# Doorbell.net
KiCad netlist of a schematic drawn in EAGLE
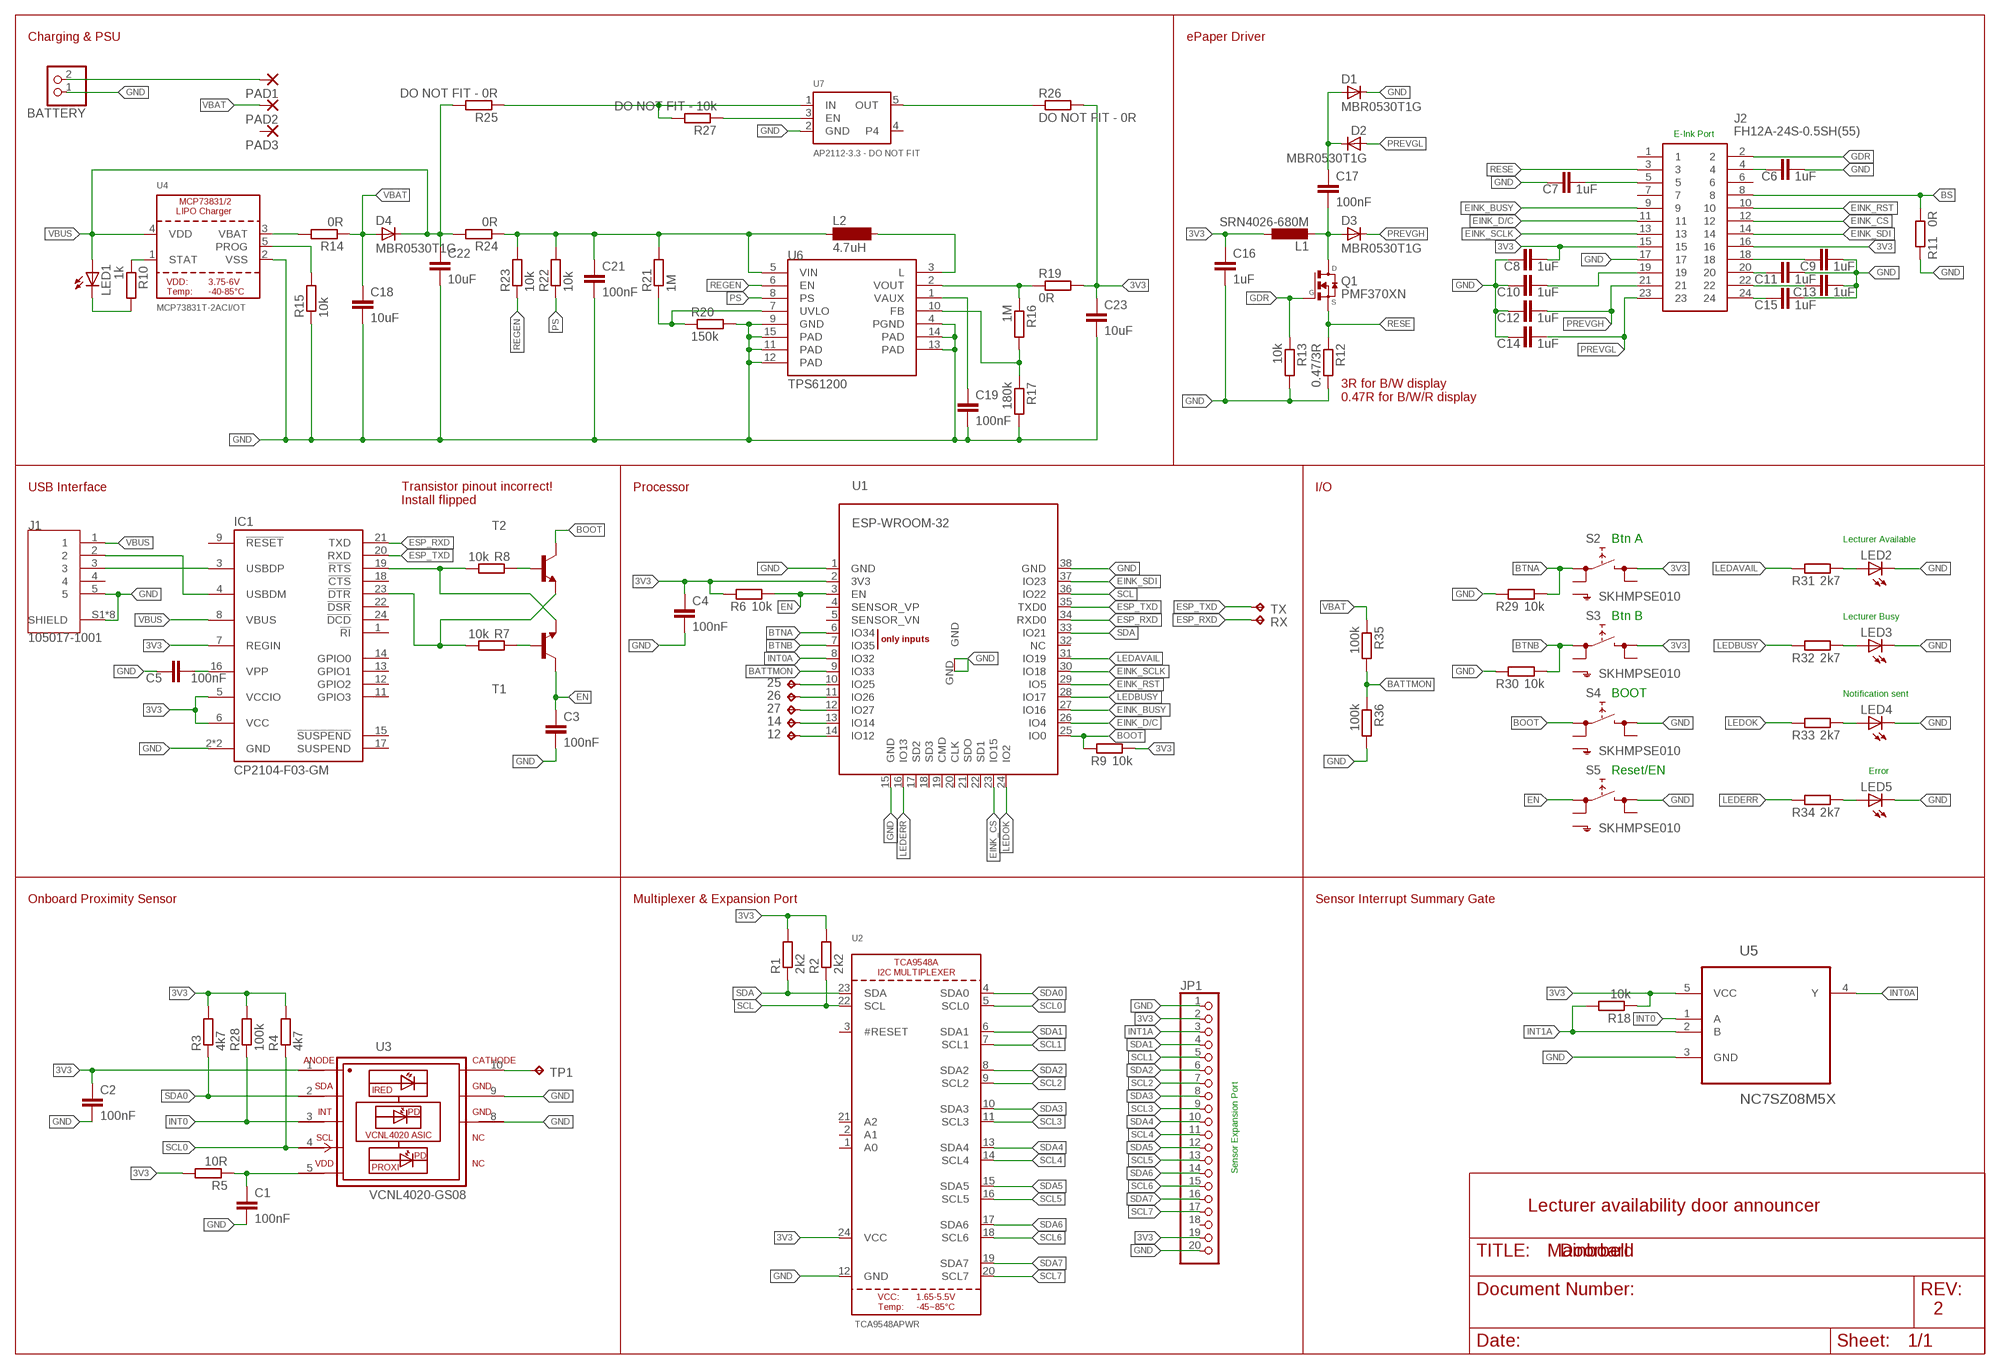
[diagram p0: schematic, sheet 1]

(export (version "E")
  (design (tool "Eeschema 10.0.6"))
  (components
    (comp (ref "12")
      (value "TPB1,27")
      (footprint "eagle-import:B1,27")
      (libsource (lib "eagle-import") (part "TPB1,27"))
    )
    (comp (ref "14")
      (value "TPB1,27")
      (footprint "eagle-import:B1,27")
      (libsource (lib "eagle-import") (part "TPB1,27"))
    )
    (comp (ref "25")
      (value "TPB1,27")
      (footprint "eagle-import:B1,27")
      (libsource (lib "eagle-import") (part "TPB1,27"))
    )
    (comp (ref "26")
      (value "TPB1,27")
      (footprint "eagle-import:B1,27")
      (libsource (lib "eagle-import") (part "TPB1,27"))
    )
    (comp (ref "27")
      (value "TPB1,27")
      (footprint "eagle-import:B1,27")
      (libsource (lib "eagle-import") (part "TPB1,27"))
    )
    (comp (ref "BATTERY")
      (value "PINHD-1X2/90")
      (footprint "eagle-import:1X02_90")
      (libsource (lib "eagle-import") (part "PINHD-1X2/90"))
    )
    (comp (ref "C1")
      (value "100nF")
      (footprint "eagle-import:C0603")
      (libsource (lib "eagle-import") (part "C-EUC0603"))
    )
    (comp (ref "C2")
      (value "100nF")
      (footprint "eagle-import:C0603")
      (libsource (lib "eagle-import") (part "C-EUC0603"))
    )
    (comp (ref "C3")
      (value "100nF")
      (footprint "eagle-import:C0603")
      (libsource (lib "eagle-import") (part "C-EUC0603"))
    )
    (comp (ref "C4")
      (value "100nF")
      (footprint "eagle-import:C0603")
      (libsource (lib "eagle-import") (part "C-EUC0603"))
    )
    (comp (ref "C5")
      (value "100nF")
      (footprint "eagle-import:C0603")
      (libsource (lib "eagle-import") (part "C-EUC0603"))
    )
    (comp (ref "C6")
      (value "1uF")
      (footprint "eagle-import:C0603")
      (libsource (lib "eagle-import") (part "C-EUC0603"))
    )
    (comp (ref "C7")
      (value "1uF")
      (footprint "eagle-import:C0603")
      (libsource (lib "eagle-import") (part "C-EUC0603"))
    )
    (comp (ref "C8")
      (value "1uF")
      (footprint "eagle-import:C0603")
      (libsource (lib "eagle-import") (part "C-EUC0603"))
    )
    (comp (ref "C9")
      (value "1uF")
      (footprint "eagle-import:C0603")
      (libsource (lib "eagle-import") (part "C-EUC0603"))
    )
    (comp (ref "C10")
      (value "1uF")
      (footprint "eagle-import:C0603")
      (libsource (lib "eagle-import") (part "C-EUC0603"))
    )
    (comp (ref "C11")
      (value "1uF")
      (footprint "eagle-import:C0603")
      (libsource (lib "eagle-import") (part "C-EUC0603"))
    )
    (comp (ref "C12")
      (value "1uF")
      (footprint "eagle-import:C0603")
      (libsource (lib "eagle-import") (part "C-EUC0603"))
    )
    (comp (ref "C13")
      (value "1uF")
      (footprint "eagle-import:C0603")
      (libsource (lib "eagle-import") (part "C-EUC0603"))
    )
    (comp (ref "C14")
      (value "1uF")
      (footprint "eagle-import:C0603")
      (libsource (lib "eagle-import") (part "C-EUC0603"))
    )
    (comp (ref "C15")
      (value "1uF")
      (footprint "eagle-import:C0603")
      (libsource (lib "eagle-import") (part "C-EUC0603"))
    )
    (comp (ref "C16")
      (value "1uF")
      (footprint "eagle-import:C0603")
      (libsource (lib "eagle-import") (part "C-EUC0603"))
    )
    (comp (ref "C17")
      (value "100nF")
      (footprint "eagle-import:C0603")
      (libsource (lib "eagle-import") (part "C-EUC0603"))
    )
    (comp (ref "C18")
      (value "10uF")
      (footprint "eagle-import:C1206")
      (libsource (lib "eagle-import") (part "C-EUC1206"))
    )
    (comp (ref "C19")
      (value "100nF")
      (footprint "eagle-import:C0603")
      (libsource (lib "eagle-import") (part "C-EUC0603"))
    )
    (comp (ref "C21")
      (value "100nF")
      (footprint "eagle-import:C0603")
      (libsource (lib "eagle-import") (part "C-EUC0603"))
    )
    (comp (ref "C22")
      (value "10uF")
      (footprint "eagle-import:C1206")
      (libsource (lib "eagle-import") (part "C-EUC1206"))
    )
    (comp (ref "C23")
      (value "10uF")
      (footprint "eagle-import:C1206")
      (libsource (lib "eagle-import") (part "C-EUC1206"))
    )
    (comp (ref "D1")
      (value "MBR0530T1G")
      (footprint "eagle-import:SOD123")
      (libsource (lib "eagle-import") (part "D-SOD123"))
    )
    (comp (ref "D2")
      (value "MBR0530T1G")
      (footprint "eagle-import:SOD123")
      (libsource (lib "eagle-import") (part "D-SOD123"))
    )
    (comp (ref "D3")
      (value "MBR0530T1G")
      (footprint "eagle-import:SOD123")
      (libsource (lib "eagle-import") (part "D-SOD123"))
    )
    (comp (ref "D4")
      (value "MBR0530T1G")
      (footprint "eagle-import:SOD123")
      (libsource (lib "eagle-import") (part "D-SOD123"))
    )
    (comp (ref "IC1")
      (value "CP2104-F03-GM")
      (footprint "eagle-import:QFN24-PAD")
      (fields (field (name "MF") "Silicon Labs") (field (name "MP") "CP2104"))
      (libsource (lib "eagle-import") (part "CP2104-F03-GM"))
    )
    (comp (ref "J1")
      (value "105017-1001")
      (footprint "eagle-import:MOLEX_105017-1001")
      (fields (field (name "MF") "Molex"))
      (libsource (lib "eagle-import") (part "105017-1001"))
    )
    (comp (ref "J2")
      (value "FH12A-24S-0.5SH(55)")
      (footprint "eagle-import:FH12A-24S-0.5SH")
      (fields (field (name "MOUSER_PART_NUMBER") "798-FH12A-24S0.5SH55"))
      (libsource (lib "eagle-import") (part "FH12A-24S-0.5SH(55)"))
    )
    (comp (ref "JP1")
      (value "PINHD-1X20/90")
      (footprint "eagle-import:1X20_90")
      (libsource (lib "eagle-import") (part "PINHD-1X20/90"))
    )
    (comp (ref "L1")
      (value "SRN4026-680M")
      (footprint "eagle-import:L4532P")
      (libsource (lib "eagle-import") (part "L-EUL4532P"))
    )
    (comp (ref "L2")
      (value "4.7uH")
      (footprint "eagle-import:MS50")
      (libsource (lib "eagle-import") (part "MS50"))
    )
    (comp (ref "LED1")
      (value "LEDSML0603")
      (footprint "eagle-import:SML0603")
      (libsource (lib "eagle-import") (part "LEDSML0603"))
    )
    (comp (ref "LED2")
      (value "LEDSML0603")
      (footprint "eagle-import:SML0603")
      (libsource (lib "eagle-import") (part "LEDSML0603"))
    )
    (comp (ref "LED3")
      (value "LEDSML0603")
      (footprint "eagle-import:SML0603")
      (libsource (lib "eagle-import") (part "LEDSML0603"))
    )
    (comp (ref "LED4")
      (value "LEDSML0603")
      (footprint "eagle-import:SML0603")
      (libsource (lib "eagle-import") (part "LEDSML0603"))
    )
    (comp (ref "LED5")
      (value "LEDSML0603")
      (footprint "eagle-import:SML0603")
      (libsource (lib "eagle-import") (part "LEDSML0603"))
    )
    (comp (ref "PAD1")
      (value "WIREPADSMD1,27-254")
      (footprint "eagle-import:SMD1,27-2,54")
      (libsource (lib "eagle-import") (part "WIREPADSMD1,27-254"))
    )
    (comp (ref "PAD2")
      (value "WIREPADSMD1,27-254")
      (footprint "eagle-import:SMD1,27-2,54")
      (libsource (lib "eagle-import") (part "WIREPADSMD1,27-254"))
    )
    (comp (ref "PAD3")
      (value "WIREPADSMD1,27-254")
      (footprint "eagle-import:SMD1,27-2,54")
      (libsource (lib "eagle-import") (part "WIREPADSMD1,27-254"))
    )
    (comp (ref "Q1")
      (value "PMF370XN")
      (footprint "eagle-import:SOT323-R")
      (fields (field (name "MF") "ON Semiconductor") (field (name "MP") "BSS138W"))
      (libsource (lib "eagle-import") (part "BSS138W"))
    )
    (comp (ref "R1")
      (value "2k2")
      (footprint "eagle-import:R0603")
      (libsource (lib "eagle-import") (part "R-EU_R0603"))
    )
    (comp (ref "R2")
      (value "2k2")
      (footprint "eagle-import:R0603")
      (libsource (lib "eagle-import") (part "R-EU_R0603"))
    )
    (comp (ref "R3")
      (value "4k7")
      (footprint "eagle-import:R0603")
      (libsource (lib "eagle-import") (part "R-EU_R0603"))
    )
    (comp (ref "R4")
      (value "4k7")
      (footprint "eagle-import:R0603")
      (libsource (lib "eagle-import") (part "R-EU_R0603"))
    )
    (comp (ref "R5")
      (value "10R")
      (footprint "eagle-import:R0603")
      (libsource (lib "eagle-import") (part "R-EU_R0603"))
    )
    (comp (ref "R6")
      (value "10k")
      (footprint "eagle-import:R0603")
      (libsource (lib "eagle-import") (part "R-EU_R0603"))
    )
    (comp (ref "R7")
      (value "10k")
      (footprint "eagle-import:R0603")
      (libsource (lib "eagle-import") (part "R-EU_R0603"))
    )
    (comp (ref "R8")
      (value "10k")
      (footprint "eagle-import:R0603")
      (libsource (lib "eagle-import") (part "R-EU_R0603"))
    )
    (comp (ref "R9")
      (value "10k")
      (footprint "eagle-import:R0603")
      (libsource (lib "eagle-import") (part "R-EU_R0603"))
    )
    (comp (ref "R10")
      (value "1k")
      (footprint "eagle-import:R0603")
      (libsource (lib "eagle-import") (part "R-EU_R0603"))
    )
    (comp (ref "R11")
      (value "0R")
      (footprint "eagle-import:R0603")
      (libsource (lib "eagle-import") (part "R-EU_R0603"))
    )
    (comp (ref "R12")
      (value "0.47/3R")
      (footprint "eagle-import:R0603")
      (libsource (lib "eagle-import") (part "R-EU_R0603"))
    )
    (comp (ref "R13")
      (value "10k")
      (footprint "eagle-import:R0603")
      (libsource (lib "eagle-import") (part "R-EU_R0603"))
    )
    (comp (ref "R14")
      (value "0R")
      (footprint "eagle-import:R0603")
      (libsource (lib "eagle-import") (part "R-EU_R0603"))
    )
    (comp (ref "R15")
      (value "10k")
      (footprint "eagle-import:R0603")
      (libsource (lib "eagle-import") (part "R-EU_R0603"))
    )
    (comp (ref "R16")
      (value "1M")
      (footprint "eagle-import:R0603")
      (libsource (lib "eagle-import") (part "R-EU_R0603"))
    )
    (comp (ref "R17")
      (value "180k")
      (footprint "eagle-import:R0603")
      (libsource (lib "eagle-import") (part "R-EU_R0603"))
    )
    (comp (ref "R18")
      (value "10k")
      (footprint "eagle-import:R0603")
      (libsource (lib "eagle-import") (part "R-EU_R0603"))
    )
    (comp (ref "R19")
      (value "0R")
      (footprint "eagle-import:R0603")
      (libsource (lib "eagle-import") (part "R-EU_R0603"))
    )
    (comp (ref "R20")
      (value "150k")
      (footprint "eagle-import:R0603")
      (libsource (lib "eagle-import") (part "R-EU_R0603"))
    )
    (comp (ref "R21")
      (value "1M")
      (footprint "eagle-import:R0603")
      (libsource (lib "eagle-import") (part "R-EU_R0603"))
    )
    (comp (ref "R22")
      (value "10k")
      (footprint "eagle-import:R0603")
      (libsource (lib "eagle-import") (part "R-EU_R0603"))
    )
    (comp (ref "R23")
      (value "10k")
      (footprint "eagle-import:R0603")
      (libsource (lib "eagle-import") (part "R-EU_R0603"))
    )
    (comp (ref "R24")
      (value "0R")
      (footprint "eagle-import:R0603")
      (libsource (lib "eagle-import") (part "R-EU_R0603"))
    )
    (comp (ref "R25")
      (value "DO NOT FIT - 0R")
      (footprint "eagle-import:R0603")
      (libsource (lib "eagle-import") (part "R-EU_R0603"))
    )
    (comp (ref "R26")
      (value "DO NOT FIT - 0R")
      (footprint "eagle-import:R0603")
      (libsource (lib "eagle-import") (part "R-EU_R0603"))
    )
    (comp (ref "R27")
      (value "DO NOT FIT - 10k")
      (footprint "eagle-import:R0603")
      (libsource (lib "eagle-import") (part "R-EU_R0603"))
    )
    (comp (ref "R28")
      (value "100k")
      (footprint "eagle-import:R0603")
      (libsource (lib "eagle-import") (part "R-EU_R0603"))
    )
    (comp (ref "R29")
      (value "10k")
      (footprint "eagle-import:R0603")
      (libsource (lib "eagle-import") (part "R-EU_R0603"))
    )
    (comp (ref "R30")
      (value "10k")
      (footprint "eagle-import:R0603")
      (libsource (lib "eagle-import") (part "R-EU_R0603"))
    )
    (comp (ref "R31")
      (value "2k7")
      (footprint "eagle-import:R0603")
      (libsource (lib "eagle-import") (part "R-EU_R0603"))
    )
    (comp (ref "R32")
      (value "2k7")
      (footprint "eagle-import:R0603")
      (libsource (lib "eagle-import") (part "R-EU_R0603"))
    )
    (comp (ref "R33")
      (value "2k7")
      (footprint "eagle-import:R0603")
      (libsource (lib "eagle-import") (part "R-EU_R0603"))
    )
    (comp (ref "R34")
      (value "2k7")
      (footprint "eagle-import:R0603")
      (libsource (lib "eagle-import") (part "R-EU_R0603"))
    )
    (comp (ref "R35")
      (value "100k")
      (footprint "eagle-import:R0603")
      (libsource (lib "eagle-import") (part "R-EU_R0603"))
    )
    (comp (ref "R36")
      (value "100k")
      (footprint "eagle-import:R0603")
      (libsource (lib "eagle-import") (part "R-EU_R0603"))
    )
    (comp (ref "RX")
      (value "TPB1,27")
      (footprint "eagle-import:B1,27")
      (libsource (lib "eagle-import") (part "TPB1,27"))
    )
    (comp (ref "S2")
      (value "SKHMPSE010")
      (footprint "eagle-import:SKHMPXE010")
      (libsource (lib "eagle-import") (part "SKHMPE010S"))
    )
    (comp (ref "S3")
      (value "SKHMPSE010")
      (footprint "eagle-import:SKHMPXE010")
      (libsource (lib "eagle-import") (part "SKHMPE010S"))
    )
    (comp (ref "S4")
      (value "SKHMPSE010")
      (footprint "eagle-import:SKHMPXE010")
      (libsource (lib "eagle-import") (part "SKHMPE010S"))
    )
    (comp (ref "S5")
      (value "SKHMPSE010")
      (footprint "eagle-import:SKHMPXE010")
      (libsource (lib "eagle-import") (part "SKHMPE010S"))
    )
    (comp (ref "T1")
      (value "-NPN-SOT23-EBC")
      (footprint "eagle-import:SOT23-EBC")
      (libsource (lib "eagle-import") (part "-NPN-SOT23-EBC"))
    )
    (comp (ref "T2")
      (value "-NPN-SOT23-EBC")
      (footprint "eagle-import:SOT23-EBC")
      (libsource (lib "eagle-import") (part "-NPN-SOT23-EBC"))
    )
    (comp (ref "TP1")
      (value "TPB1,27")
      (footprint "eagle-import:B1,27")
      (libsource (lib "eagle-import") (part "TPB1,27"))
    )
    (comp (ref "TX")
      (value "TPB1,27")
      (footprint "eagle-import:B1,27")
      (libsource (lib "eagle-import") (part "TPB1,27"))
    )
    (comp (ref "U1")
      (value "ESP-WROOM-32")
      (footprint "eagle-import:ESP-WROOM-32")
      (libsource (lib "eagle-import") (part "ESP-WROOM-32"))
    )
    (comp (ref "U2")
      (value "TCA9548APWR")
      (footprint "eagle-import:TSSOP24")
      (libsource (lib "eagle-import") (part "TCA9548A"))
    )
    (comp (ref "U3")
      (value "VCNL4020-GS08")
      (footprint "eagle-import:PHODET_VCNL4020")
      (fields (field (name "MF") "Vishay Semiconductor"))
      (libsource (lib "eagle-import") (part "VCNL4020-GS08"))
    )
    (comp (ref "U4")
      (value "MCP73831T-2ACI/OT")
      (footprint "eagle-import:SOT23-5")
      (libsource (lib "eagle-import") (part "MCP73831/2"))
    )
    (comp (ref "U5")
      (value "NC7SZ08M5X")
      (footprint "eagle-import:SOT95P280X145-5N")
      (fields
        (field (name "DIGI-KEY_PART_NUMBER") "NC7SZ08M5XCT-ND")
        (field (name "MF") "ON Semiconductor")
        (field (name "DIGI-KEY_PART_NUMBER_1") "NC7SZ08M5XCT-ND")
        (field (name "DIGI-KEY_PURCHASE_URL") "https://www.digikey.com/product-detail/en/on-semiconductor/NC7SZ08M5X/NC7SZ08M5XCT-ND/673390?utm_source=snapeda&utm_medium=aggregator&utm_campaign=symbol")
        (field (name "MP") "NC7SZ08M5X")
        (field (name "PACKAGE") "SOT-23 Texas Instruments")
      )
      (libsource (lib "eagle-import") (part "NC7SZ08M5X"))
    )
    (comp (ref "U6")
      (value "TPS61200")
      (footprint "eagle-import:QFN-10_PAD")
      (libsource (lib "eagle-import") (part "TPS61200"))
    )
    (comp (ref "U7")
      (value "AP2112-3.3 - DO NOT FIT")
      (footprint "eagle-import:SOT23-5")
      (libsource (lib "eagle-import") (part "VREG_SOT23-5"))
    )
  )
  (nets
    (net (code "1") (name "3V3") (class "Default")
      (node (ref "C16") (pin "1") (pinfunction "1_1") (pintype "passive"))
      (node (ref "C2") (pin "1") (pinfunction "1_1") (pintype "passive"))
      (node (ref "C23") (pin "1") (pinfunction "1_1") (pintype "passive"))
      (node (ref "C4") (pin "1") (pinfunction "1_1") (pintype "passive"))
      (node (ref "C8") (pin "2") (pinfunction "2_2") (pintype "passive"))
      (node (ref "IC1") (pin "5") (pinfunction "VCCIO_5") (pintype "power_in"))
      (node (ref "IC1") (pin "6") (pinfunction "VCC_6") (pintype "power_in"))
      (node (ref "IC1") (pin "7") (pinfunction "REGIN_7") (pintype "power_in"))
      (node (ref "J2") (pin "15") (pinfunction "15_15") (pintype "bidirectional"))
      (node (ref "J2") (pin "16") (pinfunction "16_16") (pintype "bidirectional"))
      (node (ref "JP1") (pin "19") (pinfunction "19_19") (pintype "passive"))
      (node (ref "JP1") (pin "2") (pinfunction "2_2") (pintype "passive"))
      (node (ref "L1") (pin "1") (pinfunction "1_1") (pintype "passive"))
      (node (ref "R1") (pin "2") (pinfunction "2_2") (pintype "passive"))
      (node (ref "R18") (pin "1") (pinfunction "1_1") (pintype "passive"))
      (node (ref "R19") (pin "2") (pinfunction "2_2") (pintype "passive"))
      (node (ref "R2") (pin "2") (pinfunction "2_2") (pintype "passive"))
      (node (ref "R26") (pin "2") (pinfunction "2_2") (pintype "passive"))
      (node (ref "R28") (pin "2") (pinfunction "2_2") (pintype "passive"))
      (node (ref "R3") (pin "2") (pinfunction "2_2") (pintype "passive"))
      (node (ref "R4") (pin "2") (pinfunction "2_2") (pintype "passive"))
      (node (ref "R5") (pin "2") (pinfunction "2_2") (pintype "passive"))
      (node (ref "R6") (pin "2") (pinfunction "2_2") (pintype "passive"))
      (node (ref "R9") (pin "1") (pinfunction "1_1") (pintype "passive"))
      (node (ref "S2") (pin "3") (pinfunction "2.1_3") (pintype "passive"))
      (node (ref "S3") (pin "3") (pinfunction "2.1_3") (pintype "passive"))
      (node (ref "U1") (pin "2") (pinfunction "3V3_2") (pintype "bidirectional"))
      (node (ref "U2") (pin "24") (pinfunction "VCC_24") (pintype "bidirectional"))
      (node (ref "U3") (pin "1") (pinfunction "IR-ANODE_1") (pintype "passive"))
      (node (ref "U5") (pin "5") (pinfunction "VCC_5") (pintype "power_in"))
    )
    (net (code "2") (name "BATTMON") (class "Default")
      (node (ref "R35") (pin "2") (pinfunction "2_2") (pintype "passive"))
      (node (ref "R36") (pin "1") (pinfunction "1_1") (pintype "passive"))
      (node (ref "U1") (pin "9") (pinfunction "IO33_9") (pintype "bidirectional"))
    )
    (net (code "3") (name "BOOT") (class "Default")
      (node (ref "R9") (pin "2") (pinfunction "2_2") (pintype "passive"))
      (node (ref "S4") (pin "1") (pinfunction "1.1_1") (pintype "passive"))
      (node (ref "T2") (pin "C") (pinfunction "C_C") (pintype "passive"))
      (node (ref "U1") (pin "25") (pinfunction "IO0_25") (pintype "bidirectional"))
    )
    (net (code "4") (name "BS") (class "Default")
      (node (ref "J2") (pin "8") (pinfunction "8_8") (pintype "bidirectional"))
      (node (ref "R11") (pin "1") (pinfunction "1_1") (pintype "passive"))
    )
    (net (code "5") (name "BTNA") (class "Default")
      (node (ref "R29") (pin "1") (pinfunction "1_1") (pintype "passive"))
      (node (ref "S2") (pin "1") (pinfunction "1.1_1") (pintype "passive"))
      (node (ref "U1") (pin "6") (pinfunction "IO34_6") (pintype "input"))
    )
    (net (code "6") (name "BTNB") (class "Default")
      (node (ref "R30") (pin "1") (pinfunction "1_1") (pintype "passive"))
      (node (ref "S3") (pin "1") (pinfunction "1.1_1") (pintype "passive"))
      (node (ref "U1") (pin "7") (pinfunction "IO35_7") (pintype "input"))
    )
    (net (code "7") (name "EINK_BUSY") (class "Default")
      (node (ref "J2") (pin "9") (pinfunction "9_9") (pintype "bidirectional"))
      (node (ref "U1") (pin "27") (pinfunction "IO16_27") (pintype "bidirectional"))
    )
    (net (code "8") (name "EINK_CS") (class "Default")
      (node (ref "J2") (pin "12") (pinfunction "12_12") (pintype "bidirectional"))
      (node (ref "U1") (pin "23") (pinfunction "IO15_23") (pintype "bidirectional"))
    )
    (net (code "9") (name "EINK_D{slash}C") (class "Default")
      (node (ref "J2") (pin "11") (pinfunction "11_11") (pintype "bidirectional"))
      (node (ref "U1") (pin "26") (pinfunction "IO4_26") (pintype "bidirectional"))
    )
    (net (code "10") (name "EINK_RST") (class "Default")
      (node (ref "J2") (pin "10") (pinfunction "10_10") (pintype "bidirectional"))
      (node (ref "U1") (pin "29") (pinfunction "IO5_29") (pintype "bidirectional"))
    )
    (net (code "11") (name "EINK_SCLK") (class "Default")
      (node (ref "J2") (pin "13") (pinfunction "13_13") (pintype "bidirectional"))
      (node (ref "U1") (pin "30") (pinfunction "IO18_30") (pintype "bidirectional"))
    )
    (net (code "12") (name "EINK_SDI") (class "Default")
      (node (ref "J2") (pin "14") (pinfunction "14_14") (pintype "bidirectional"))
      (node (ref "U1") (pin "37") (pinfunction "IO23_37") (pintype "bidirectional"))
    )
    (net (code "13") (name "EN") (class "Default")
      (node (ref "C3") (pin "1") (pinfunction "1_1") (pintype "passive"))
      (node (ref "R6") (pin "1") (pinfunction "1_1") (pintype "passive"))
      (node (ref "S5") (pin "1") (pinfunction "1.1_1") (pintype "passive"))
      (node (ref "T1") (pin "C") (pinfunction "C_C") (pintype "passive"))
      (node (ref "U1") (pin "3") (pinfunction "EN_3") (pintype "bidirectional"))
    )
    (net (code "14") (name "ESP_RXD") (class "Default")
      (node (ref "IC1") (pin "21") (pinfunction "TXD_21") (pintype "bidirectional"))
      (node (ref "RX") (pin "TP") (pinfunction "TP_TP") (pintype "input"))
      (node (ref "U1") (pin "34") (pinfunction "RXD0_34") (pintype "bidirectional"))
    )
    (net (code "15") (name "ESP_TXD") (class "Default")
      (node (ref "IC1") (pin "20") (pinfunction "RXD_20") (pintype "bidirectional"))
      (node (ref "TX") (pin "TP") (pinfunction "TP_TP") (pintype "input"))
      (node (ref "U1") (pin "35") (pinfunction "TXD0_35") (pintype "bidirectional"))
    )
    (net (code "16") (name "GDR") (class "Default")
      (node (ref "J2") (pin "2") (pinfunction "2_2") (pintype "bidirectional"))
      (node (ref "Q1") (pin "1") (pinfunction "G_1") (pintype "passive"))
      (node (ref "R13") (pin "1") (pinfunction "1_1") (pintype "passive"))
    )
    (net (code "17") (name "GND") (class "Default")
      (node (ref "BATTERY") (pin "1") (pinfunction "1_1") (pintype "passive"))
      (node (ref "C1") (pin "2") (pinfunction "2_2") (pintype "passive"))
      (node (ref "C10") (pin "1") (pinfunction "1_1") (pintype "passive"))
      (node (ref "C11") (pin "2") (pinfunction "2_2") (pintype "passive"))
      (node (ref "C12") (pin "1") (pinfunction "1_1") (pintype "passive"))
      (node (ref "C13") (pin "2") (pinfunction "2_2") (pintype "passive"))
      (node (ref "C14") (pin "1") (pinfunction "1_1") (pintype "passive"))
      (node (ref "C15") (pin "2") (pinfunction "2_2") (pintype "passive"))
      (node (ref "C16") (pin "2") (pinfunction "2_2") (pintype "passive"))
      (node (ref "C18") (pin "2") (pinfunction "2_2") (pintype "passive"))
      (node (ref "C19") (pin "2") (pinfunction "2_2") (pintype "passive"))
      (node (ref "C2") (pin "2") (pinfunction "2_2") (pintype "passive"))
      (node (ref "C21") (pin "2") (pinfunction "2_2") (pintype "passive"))
      (node (ref "C22") (pin "2") (pinfunction "2_2") (pintype "passive"))
      (node (ref "C23") (pin "2") (pinfunction "2_2") (pintype "passive"))
      (node (ref "C3") (pin "2") (pinfunction "2_2") (pintype "passive"))
      (node (ref "C4") (pin "2") (pinfunction "2_2") (pintype "passive"))
      (node (ref "C5") (pin "1") (pinfunction "1_1") (pintype "passive"))
      (node (ref "C6") (pin "2") (pinfunction "2_2") (pintype "passive"))
      (node (ref "C7") (pin "1") (pinfunction "1_1") (pintype "passive"))
      (node (ref "C8") (pin "1") (pinfunction "1_1") (pintype "passive"))
      (node (ref "C9") (pin "2") (pinfunction "2_2") (pintype "passive"))
      (node (ref "D1") (pin "1") (pinfunction "C_1") (pintype "passive"))
      (node (ref "IC1") (pin "2") (pinfunction "GND_2") (pintype "power_in"))
      (node (ref "IC1") (pin "TP") (pinfunction "GND_TP") (pintype "power_in"))
      (node (ref "J1") (pin "5") (pinfunction "5_5") (pintype "passive"))
      (node (ref "J1") (pin "S1") (pinfunction "SHIELD_S1") (pintype "passive"))
      (node (ref "J1") (pin "S1.1") (pinfunction "SHIELD_S1.1") (pintype "passive"))
      (node (ref "J1") (pin "S2") (pinfunction "SHIELD_S2") (pintype "passive"))
      (node (ref "J1") (pin "S2.1") (pinfunction "SHIELD_S2.1") (pintype "passive"))
      (node (ref "J1") (pin "S3") (pinfunction "SHIELD_S3") (pintype "passive"))
      (node (ref "J1") (pin "S4") (pinfunction "SHIELD_S4") (pintype "passive"))
      (node (ref "J1") (pin "S5") (pinfunction "SHIELD_S5") (pintype "passive"))
      (node (ref "J1") (pin "S6") (pinfunction "SHIELD_S6") (pintype "passive"))
      (node (ref "J2") (pin "17") (pinfunction "17_17") (pintype "bidirectional"))
      (node (ref "JP1") (pin "1") (pinfunction "1_1") (pintype "passive"))
      (node (ref "JP1") (pin "20") (pinfunction "20_20") (pintype "passive"))
      (node (ref "LED2") (pin "C") (pinfunction "C_C") (pintype "passive"))
      (node (ref "LED3") (pin "C") (pinfunction "C_C") (pintype "passive"))
      (node (ref "LED4") (pin "C") (pinfunction "C_C") (pintype "passive"))
      (node (ref "LED5") (pin "C") (pinfunction "C_C") (pintype "passive"))
      (node (ref "R11") (pin "2") (pinfunction "2_2") (pintype "passive"))
      (node (ref "R12") (pin "2") (pinfunction "2_2") (pintype "passive"))
      (node (ref "R13") (pin "2") (pinfunction "2_2") (pintype "passive"))
      (node (ref "R15") (pin "1") (pinfunction "1_1") (pintype "passive"))
      (node (ref "R17") (pin "2") (pinfunction "2_2") (pintype "passive"))
      (node (ref "R20") (pin "2") (pinfunction "2_2") (pintype "passive"))
      (node (ref "R29") (pin "2") (pinfunction "2_2") (pintype "passive"))
      (node (ref "R30") (pin "2") (pinfunction "2_2") (pintype "passive"))
      (node (ref "R36") (pin "2") (pinfunction "2_2") (pintype "passive"))
      (node (ref "S4") (pin "3") (pinfunction "2.1_3") (pintype "passive"))
      (node (ref "S5") (pin "3") (pinfunction "2.1_3") (pintype "passive"))
      (node (ref "U1") (pin "1") (pinfunction "GND_1") (pintype "bidirectional"))
      (node (ref "U1") (pin "15") (pinfunction "GND_15") (pintype "bidirectional"))
      (node (ref "U1") (pin "38") (pinfunction "GND_38") (pintype "bidirectional"))
      (node (ref "U1") (pin "GND") (pinfunction "GND_GND") (pintype "bidirectional"))
      (node (ref "U2") (pin "12") (pinfunction "GND_12") (pintype "bidirectional"))
      (node (ref "U3") (pin "8") (pinfunction "GND2_8") (pintype "power_in"))
      (node (ref "U3") (pin "9") (pinfunction "GND_9") (pintype "power_in"))
      (node (ref "U4") (pin "2") (pinfunction "VSS_2") (pintype "power_in"))
      (node (ref "U5") (pin "3") (pinfunction "GND_3") (pintype "passive"))
      (node (ref "U6") (pin "11") (pinfunction "PAD_11") (pintype "power_in"))
      (node (ref "U6") (pin "12") (pinfunction "PAD_12") (pintype "power_in"))
      (node (ref "U6") (pin "13") (pinfunction "PAD_13") (pintype "power_in"))
      (node (ref "U6") (pin "14") (pinfunction "PAD_14") (pintype "power_in"))
      (node (ref "U6") (pin "15") (pinfunction "PAD_15") (pintype "power_in"))
      (node (ref "U6") (pin "4") (pinfunction "PGND_4") (pintype "power_in"))
      (node (ref "U6") (pin "9") (pinfunction "GND_9") (pintype "power_in"))
      (node (ref "U7") (pin "2") (pinfunction "GND_2") (pintype "power_in"))
    )
    (net (code "18") (name "INT0") (class "Default")
      (node (ref "R28") (pin "1") (pinfunction "1_1") (pintype "passive"))
      (node (ref "U3") (pin "3") (pinfunction "INT_3") (pintype "output"))
      (node (ref "U5") (pin "1") (pinfunction "A_1") (pintype "input"))
    )
    (net (code "19") (name "INT0A") (class "Default")
      (node (ref "U1") (pin "8") (pinfunction "IO32_8") (pintype "bidirectional"))
      (node (ref "U5") (pin "4") (pinfunction "Y_4") (pintype "output"))
    )
    (net (code "20") (name "INT1A") (class "Default")
      (node (ref "JP1") (pin "3") (pinfunction "3_3") (pintype "passive"))
      (node (ref "R18") (pin "2") (pinfunction "2_2") (pintype "passive"))
      (node (ref "U5") (pin "2") (pinfunction "B_2") (pintype "input"))
    )
    (net (code "21") (name "LEDAVAIL") (class "Default")
      (node (ref "R31") (pin "2") (pinfunction "2_2") (pintype "passive"))
      (node (ref "U1") (pin "31") (pinfunction "IO19_31") (pintype "bidirectional"))
    )
    (net (code "22") (name "LEDBUSY") (class "Default")
      (node (ref "R32") (pin "2") (pinfunction "2_2") (pintype "passive"))
      (node (ref "U1") (pin "28") (pinfunction "IO17_28") (pintype "bidirectional"))
    )
    (net (code "23") (name "LEDERR") (class "Default")
      (node (ref "R34") (pin "2") (pinfunction "2_2") (pintype "passive"))
      (node (ref "U1") (pin "16") (pinfunction "IO13_16") (pintype "bidirectional"))
    )
    (net (code "24") (name "LEDOK") (class "Default")
      (node (ref "R33") (pin "2") (pinfunction "2_2") (pintype "passive"))
      (node (ref "U1") (pin "24") (pinfunction "IO2_24") (pintype "bidirectional"))
    )
    (net (code "25") (name "Net-(C6-Pad1)") (class "Default")
      (node (ref "C6") (pin "1") (pinfunction "1_1") (pintype "passive"))
      (node (ref "J2") (pin "4") (pinfunction "4_4") (pintype "bidirectional"))
    )
    (net (code "26") (name "Net-(C7-Pad2)") (class "Default")
      (node (ref "C7") (pin "2") (pinfunction "2_2") (pintype "passive"))
      (node (ref "J2") (pin "5") (pinfunction "5_5") (pintype "bidirectional"))
    )
    (net (code "27") (name "Net-(C9-Pad1)") (class "Default")
      (node (ref "C9") (pin "1") (pinfunction "1_1") (pintype "passive"))
      (node (ref "J2") (pin "18") (pinfunction "18_18") (pintype "bidirectional"))
    )
    (net (code "28") (name "Net-(C10-Pad2)") (class "Default")
      (node (ref "C10") (pin "2") (pinfunction "2_2") (pintype "passive"))
      (node (ref "J2") (pin "19") (pinfunction "19_19") (pintype "bidirectional"))
    )
    (net (code "29") (name "Net-(C11-Pad1)") (class "Default")
      (node (ref "C11") (pin "1") (pinfunction "1_1") (pintype "passive"))
      (node (ref "J2") (pin "20") (pinfunction "20_20") (pintype "bidirectional"))
    )
    (net (code "30") (name "Net-(C13-Pad1)") (class "Default")
      (node (ref "C13") (pin "1") (pinfunction "1_1") (pintype "passive"))
      (node (ref "J2") (pin "22") (pinfunction "22_22") (pintype "bidirectional"))
    )
    (net (code "31") (name "Net-(C15-Pad1)") (class "Default")
      (node (ref "C15") (pin "1") (pinfunction "1_1") (pintype "passive"))
      (node (ref "J2") (pin "24") (pinfunction "24_24") (pintype "bidirectional"))
    )
    (net (code "32") (name "Net-(D1-A)") (class "Default")
      (node (ref "C17") (pin "1") (pinfunction "1_1") (pintype "passive"))
      (node (ref "D1") (pin "2") (pinfunction "A_2") (pintype "passive"))
      (node (ref "D2") (pin "1") (pinfunction "C_1") (pintype "passive"))
    )
    (net (code "33") (name "Net-(D3-A)") (class "Default")
      (node (ref "C17") (pin "2") (pinfunction "2_2") (pintype "passive"))
      (node (ref "D3") (pin "2") (pinfunction "A_2") (pintype "passive"))
      (node (ref "L1") (pin "2") (pinfunction "2_2") (pintype "passive"))
      (node (ref "Q1") (pin "3") (pinfunction "D_3") (pintype "passive"))
    )
    (net (code "34") (name "Net-(IC1-USBDM)") (class "Default")
      (node (ref "IC1") (pin "4") (pinfunction "USBDM_4") (pintype "bidirectional"))
      (node (ref "J1") (pin "2") (pinfunction "2_2") (pintype "passive"))
    )
    (net (code "35") (name "Net-(IC1-USBDP)") (class "Default")
      (node (ref "IC1") (pin "3") (pinfunction "USBDP_3") (pintype "bidirectional"))
      (node (ref "J1") (pin "3") (pinfunction "3_3") (pintype "passive"))
    )
    (net (code "36") (name "Net-(IC1-VPP)") (class "Default")
      (node (ref "C5") (pin "2") (pinfunction "2_2") (pintype "passive"))
      (node (ref "IC1") (pin "16") (pinfunction "VPP_16") (pintype "power_in"))
    )
    (net (code "37") (name "Net-(IC1-~{DTR})") (class "Default")
      (node (ref "IC1") (pin "23") (pinfunction "~{DTR}_23") (pintype "bidirectional"))
      (node (ref "R7") (pin "1") (pinfunction "1_1") (pintype "passive"))
      (node (ref "T2") (pin "E") (pinfunction "E_E") (pintype "passive"))
    )
    (net (code "38") (name "Net-(IC1-~{RTS})") (class "Default")
      (node (ref "IC1") (pin "19") (pinfunction "~{RTS}_19") (pintype "bidirectional"))
      (node (ref "R8") (pin "1") (pinfunction "1_1") (pintype "passive"))
      (node (ref "T1") (pin "E") (pinfunction "E_E") (pintype "passive"))
    )
    (net (code "39") (name "Net-(LED1-PadC)") (class "Default")
      (node (ref "LED1") (pin "C") (pinfunction "C_C") (pintype "passive"))
      (node (ref "R10") (pin "2") (pinfunction "2_2") (pintype "passive"))
    )
    (net (code "40") (name "Net-(LED2-PadA)") (class "Default")
      (node (ref "LED2") (pin "A") (pinfunction "A_A") (pintype "passive"))
      (node (ref "R31") (pin "1") (pinfunction "1_1") (pintype "passive"))
    )
    (net (code "41") (name "Net-(LED3-PadA)") (class "Default")
      (node (ref "LED3") (pin "A") (pinfunction "A_A") (pintype "passive"))
      (node (ref "R32") (pin "1") (pinfunction "1_1") (pintype "passive"))
    )
    (net (code "42") (name "Net-(LED4-PadA)") (class "Default")
      (node (ref "LED4") (pin "A") (pinfunction "A_A") (pintype "passive"))
      (node (ref "R33") (pin "1") (pinfunction "1_1") (pintype "passive"))
    )
    (net (code "43") (name "Net-(LED5-PadA)") (class "Default")
      (node (ref "LED5") (pin "A") (pinfunction "A_A") (pintype "passive"))
      (node (ref "R34") (pin "1") (pinfunction "1_1") (pintype "passive"))
    )
    (net (code "44") (name "Net-(PAD1-P)") (class "Default")
      (node (ref "BATTERY") (pin "2") (pinfunction "2_2") (pintype "passive"))
      (node (ref "PAD1") (pin "1") (pinfunction "P_1") (pintype "passive"))
    )
    (net (code "45") (name "Net-(R7-Pad2)") (class "Default")
      (node (ref "R7") (pin "2") (pinfunction "2_2") (pintype "passive"))
      (node (ref "T1") (pin "B") (pinfunction "B_B") (pintype "passive"))
    )
    (net (code "46") (name "Net-(R8-Pad2)") (class "Default")
      (node (ref "R8") (pin "2") (pinfunction "2_2") (pintype "passive"))
      (node (ref "T2") (pin "B") (pinfunction "B_B") (pintype "passive"))
    )
    (net (code "47") (name "Net-(U1-IO12)") (class "Default")
      (node (ref "12") (pin "TP") (pinfunction "TP_TP") (pintype "input"))
      (node (ref "U1") (pin "14") (pinfunction "IO12_14") (pintype "bidirectional"))
    )
    (net (code "48") (name "Net-(U1-IO14)") (class "Default")
      (node (ref "14") (pin "TP") (pinfunction "TP_TP") (pintype "input"))
      (node (ref "U1") (pin "13") (pinfunction "IO14_13") (pintype "bidirectional"))
    )
    (net (code "49") (name "Net-(U1-IO25)") (class "Default")
      (node (ref "25") (pin "TP") (pinfunction "TP_TP") (pintype "input"))
      (node (ref "U1") (pin "10") (pinfunction "IO25_10") (pintype "bidirectional"))
    )
    (net (code "50") (name "Net-(U1-IO26)") (class "Default")
      (node (ref "26") (pin "TP") (pinfunction "TP_TP") (pintype "input"))
      (node (ref "U1") (pin "11") (pinfunction "IO26_11") (pintype "bidirectional"))
    )
    (net (code "51") (name "Net-(U1-IO27)") (class "Default")
      (node (ref "27") (pin "TP") (pinfunction "TP_TP") (pintype "input"))
      (node (ref "U1") (pin "12") (pinfunction "IO27_12") (pintype "bidirectional"))
    )
    (net (code "52") (name "Net-(U3-IR-CATHODE)") (class "Default")
      (node (ref "TP1") (pin "TP") (pinfunction "TP_TP") (pintype "input"))
      (node (ref "U3") (pin "10") (pinfunction "IR-CATHODE_10") (pintype "passive"))
    )
    (net (code "53") (name "Net-(U3-VDD)") (class "Default")
      (node (ref "C1") (pin "1") (pinfunction "1_1") (pintype "passive"))
      (node (ref "R5") (pin "1") (pinfunction "1_1") (pintype "passive"))
      (node (ref "U3") (pin "5") (pinfunction "VDD_5") (pintype "power_in"))
    )
    (net (code "54") (name "Net-(U4-PROG)") (class "Default")
      (node (ref "R15") (pin "2") (pinfunction "2_2") (pintype "passive"))
      (node (ref "U4") (pin "5") (pinfunction "PROG_5") (pintype "input"))
    )
    (net (code "55") (name "Net-(U4-STAT)") (class "Default")
      (node (ref "R10") (pin "1") (pinfunction "1_1") (pintype "passive"))
      (node (ref "U4") (pin "1") (pinfunction "STAT_1") (pintype "output"))
    )
    (net (code "56") (name "Net-(U4-VBAT)") (class "Default")
      (node (ref "R14") (pin "2") (pinfunction "2_2") (pintype "passive"))
      (node (ref "U4") (pin "3") (pinfunction "VBAT_3") (pintype "power_in"))
    )
    (net (code "57") (name "Net-(U6-FB)") (class "Default")
      (node (ref "R16") (pin "2") (pinfunction "2_2") (pintype "passive"))
      (node (ref "R17") (pin "1") (pinfunction "1_1") (pintype "passive"))
      (node (ref "U6") (pin "10") (pinfunction "FB_10") (pintype "passive"))
    )
    (net (code "58") (name "Net-(U6-L)") (class "Default")
      (node (ref "L2") (pin "2") (pinfunction "2_2") (pintype "passive"))
      (node (ref "U6") (pin "3") (pinfunction "L_3") (pintype "passive"))
    )
    (net (code "59") (name "Net-(U6-UVLO)") (class "Default")
      (node (ref "R20") (pin "1") (pinfunction "1_1") (pintype "passive"))
      (node (ref "R21") (pin "1") (pinfunction "1_1") (pintype "passive"))
      (node (ref "U6") (pin "7") (pinfunction "UVLO_7") (pintype "passive"))
    )
    (net (code "60") (name "Net-(U6-VAUX)") (class "Default")
      (node (ref "C19") (pin "1") (pinfunction "1_1") (pintype "passive"))
      (node (ref "U6") (pin "1") (pinfunction "VAUX_1") (pintype "passive"))
    )
    (net (code "61") (name "Net-(U6-VIN)") (class "Default")
      (node (ref "C21") (pin "1") (pinfunction "1_1") (pintype "passive"))
      (node (ref "L2") (pin "1") (pinfunction "1_1") (pintype "passive"))
      (node (ref "R21") (pin "2") (pinfunction "2_2") (pintype "passive"))
      (node (ref "R22") (pin "2") (pinfunction "2_2") (pintype "passive"))
      (node (ref "R23") (pin "2") (pinfunction "2_2") (pintype "passive"))
      (node (ref "R24") (pin "1") (pinfunction "1_1") (pintype "passive"))
      (node (ref "U6") (pin "5") (pinfunction "VIN_5") (pintype "power_in"))
    )
    (net (code "62") (name "Net-(U6-VOUT)") (class "Default")
      (node (ref "R16") (pin "1") (pinfunction "1_1") (pintype "passive"))
      (node (ref "R19") (pin "1") (pinfunction "1_1") (pintype "passive"))
      (node (ref "U6") (pin "2") (pinfunction "VOUT_2") (pintype "passive"))
    )
    (net (code "63") (name "Net-(U7-EN)") (class "Default")
      (node (ref "R27") (pin "1") (pinfunction "1_1") (pintype "passive"))
      (node (ref "U7") (pin "3") (pinfunction "EN_3") (pintype "input"))
    )
    (net (code "64") (name "Net-(U7-IN)") (class "Default")
      (node (ref "R25") (pin "1") (pinfunction "1_1") (pintype "passive"))
      (node (ref "R27") (pin "2") (pinfunction "2_2") (pintype "passive"))
      (node (ref "U7") (pin "1") (pinfunction "IN_1") (pintype "power_in"))
    )
    (net (code "65") (name "Net-(U7-OUT)") (class "Default")
      (node (ref "R26") (pin "1") (pinfunction "1_1") (pintype "passive"))
      (node (ref "U7") (pin "5") (pinfunction "OUT_5") (pintype "power_in"))
    )
    (net (code "66") (name "PREVGH") (class "Default")
      (node (ref "C12") (pin "2") (pinfunction "2_2") (pintype "passive"))
      (node (ref "D3") (pin "1") (pinfunction "C_1") (pintype "passive"))
      (node (ref "J2") (pin "21") (pinfunction "21_21") (pintype "bidirectional"))
    )
    (net (code "67") (name "PREVGL") (class "Default")
      (node (ref "C14") (pin "2") (pinfunction "2_2") (pintype "passive"))
      (node (ref "D2") (pin "2") (pinfunction "A_2") (pintype "passive"))
      (node (ref "J2") (pin "23") (pinfunction "23_23") (pintype "bidirectional"))
    )
    (net (code "68") (name "PS") (class "Default")
      (node (ref "R22") (pin "1") (pinfunction "1_1") (pintype "passive"))
      (node (ref "U6") (pin "8") (pinfunction "PS_8") (pintype "input"))
    )
    (net (code "69") (name "REGEN") (class "Default")
      (node (ref "R23") (pin "1") (pinfunction "1_1") (pintype "passive"))
      (node (ref "U6") (pin "6") (pinfunction "EN_6") (pintype "input"))
    )
    (net (code "70") (name "RESE") (class "Default")
      (node (ref "J2") (pin "3") (pinfunction "3_3") (pintype "bidirectional"))
      (node (ref "Q1") (pin "2") (pinfunction "S_2") (pintype "passive"))
      (node (ref "R12") (pin "1") (pinfunction "1_1") (pintype "passive"))
    )
    (net (code "71") (name "SCL") (class "Default")
      (node (ref "R2") (pin "1") (pinfunction "1_1") (pintype "passive"))
      (node (ref "U1") (pin "36") (pinfunction "IO22_36") (pintype "bidirectional"))
      (node (ref "U2") (pin "22") (pinfunction "SCL_22") (pintype "bidirectional"))
    )
    (net (code "72") (name "SCL0") (class "Default")
      (node (ref "R4") (pin "1") (pinfunction "1_1") (pintype "passive"))
      (node (ref "U2") (pin "5") (pinfunction "SCL0_5") (pintype "bidirectional"))
      (node (ref "U3") (pin "4") (pinfunction "SCL_4") (pintype "input"))
    )
    (net (code "73") (name "SCL1") (class "Default")
      (node (ref "JP1") (pin "5") (pinfunction "5_5") (pintype "passive"))
      (node (ref "U2") (pin "7") (pinfunction "SCL1_7") (pintype "bidirectional"))
    )
    (net (code "74") (name "SCL2") (class "Default")
      (node (ref "JP1") (pin "7") (pinfunction "7_7") (pintype "passive"))
      (node (ref "U2") (pin "9") (pinfunction "SCL2_9") (pintype "bidirectional"))
    )
    (net (code "75") (name "SCL3") (class "Default")
      (node (ref "JP1") (pin "9") (pinfunction "9_9") (pintype "passive"))
      (node (ref "U2") (pin "11") (pinfunction "SCL3_11") (pintype "bidirectional"))
    )
    (net (code "76") (name "SCL4") (class "Default")
      (node (ref "JP1") (pin "11") (pinfunction "11_11") (pintype "passive"))
      (node (ref "U2") (pin "14") (pinfunction "SCL4_14") (pintype "bidirectional"))
    )
    (net (code "77") (name "SCL5") (class "Default")
      (node (ref "JP1") (pin "13") (pinfunction "13_13") (pintype "passive"))
      (node (ref "U2") (pin "16") (pinfunction "SCL5_16") (pintype "bidirectional"))
    )
    (net (code "78") (name "SCL6") (class "Default")
      (node (ref "JP1") (pin "15") (pinfunction "15_15") (pintype "passive"))
      (node (ref "U2") (pin "18") (pinfunction "SCL6_18") (pintype "bidirectional"))
    )
    (net (code "79") (name "SCL7") (class "Default")
      (node (ref "JP1") (pin "17") (pinfunction "17_17") (pintype "passive"))
      (node (ref "U2") (pin "20") (pinfunction "SCL7_20") (pintype "bidirectional"))
    )
    (net (code "80") (name "SDA") (class "Default")
      (node (ref "R1") (pin "1") (pinfunction "1_1") (pintype "passive"))
      (node (ref "U1") (pin "33") (pinfunction "IO21_33") (pintype "bidirectional"))
      (node (ref "U2") (pin "23") (pinfunction "SDA_23") (pintype "bidirectional"))
    )
    (net (code "81") (name "SDA0") (class "Default")
      (node (ref "R3") (pin "1") (pinfunction "1_1") (pintype "passive"))
      (node (ref "U2") (pin "4") (pinfunction "SDA0_4") (pintype "bidirectional"))
      (node (ref "U3") (pin "2") (pinfunction "SDA_2") (pintype "bidirectional"))
    )
    (net (code "82") (name "SDA1") (class "Default")
      (node (ref "JP1") (pin "4") (pinfunction "4_4") (pintype "passive"))
      (node (ref "U2") (pin "6") (pinfunction "SDA1_6") (pintype "bidirectional"))
    )
    (net (code "83") (name "SDA2") (class "Default")
      (node (ref "JP1") (pin "6") (pinfunction "6_6") (pintype "passive"))
      (node (ref "U2") (pin "8") (pinfunction "SDA2_8") (pintype "bidirectional"))
    )
    (net (code "84") (name "SDA3") (class "Default")
      (node (ref "JP1") (pin "8") (pinfunction "8_8") (pintype "passive"))
      (node (ref "U2") (pin "10") (pinfunction "SDA3_10") (pintype "bidirectional"))
    )
    (net (code "85") (name "SDA4") (class "Default")
      (node (ref "JP1") (pin "10") (pinfunction "10_10") (pintype "passive"))
      (node (ref "U2") (pin "13") (pinfunction "SDA4_13") (pintype "bidirectional"))
    )
    (net (code "86") (name "SDA5") (class "Default")
      (node (ref "JP1") (pin "12") (pinfunction "12_12") (pintype "passive"))
      (node (ref "U2") (pin "15") (pinfunction "SDA5_15") (pintype "bidirectional"))
    )
    (net (code "87") (name "SDA6") (class "Default")
      (node (ref "JP1") (pin "14") (pinfunction "14_14") (pintype "passive"))
      (node (ref "U2") (pin "17") (pinfunction "SDA6_17") (pintype "bidirectional"))
    )
    (net (code "88") (name "SDA7") (class "Default")
      (node (ref "JP1") (pin "16") (pinfunction "16_16") (pintype "passive"))
      (node (ref "U2") (pin "19") (pinfunction "SDA7_19") (pintype "bidirectional"))
    )
    (net (code "89") (name "VBAT") (class "Default")
      (node (ref "C18") (pin "1") (pinfunction "1_1") (pintype "passive"))
      (node (ref "D4") (pin "2") (pinfunction "A_2") (pintype "passive"))
      (node (ref "PAD2") (pin "1") (pinfunction "P_1") (pintype "passive"))
      (node (ref "R14") (pin "1") (pinfunction "1_1") (pintype "passive"))
      (node (ref "R35") (pin "1") (pinfunction "1_1") (pintype "passive"))
    )
    (net (code "90") (name "VBUS") (class "Default")
      (node (ref "C22") (pin "1") (pinfunction "1_1") (pintype "passive"))
      (node (ref "D4") (pin "1") (pinfunction "C_1") (pintype "passive"))
      (node (ref "IC1") (pin "8") (pinfunction "VBUS_8") (pintype "power_in"))
      (node (ref "J1") (pin "1") (pinfunction "1_1") (pintype "passive"))
      (node (ref "LED1") (pin "A") (pinfunction "A_A") (pintype "passive"))
      (node (ref "R24") (pin "2") (pinfunction "2_2") (pintype "passive"))
      (node (ref "R25") (pin "2") (pinfunction "2_2") (pintype "passive"))
      (node (ref "U4") (pin "4") (pinfunction "VDD_4") (pintype "power_in"))
    )
    (net (code "91") (name "unconnected-(IC1-GPIO0-Pad14)") (class "Default")
      (node (ref "IC1") (pin "14") (pinfunction "GPIO0_14") (pintype "bidirectional"))
    )
    (net (code "92") (name "unconnected-(IC1-GPIO1-Pad13)") (class "Default")
      (node (ref "IC1") (pin "13") (pinfunction "GPIO1_13") (pintype "bidirectional"))
    )
    (net (code "93") (name "unconnected-(IC1-GPIO2-Pad12)") (class "Default")
      (node (ref "IC1") (pin "12") (pinfunction "GPIO2_12") (pintype "bidirectional"))
    )
    (net (code "94") (name "unconnected-(IC1-GPIO3-Pad11)") (class "Default")
      (node (ref "IC1") (pin "11") (pinfunction "GPIO3_11") (pintype "bidirectional"))
    )
    (net (code "95") (name "unconnected-(IC1-SUSPEND-Pad17)") (class "Default")
      (node (ref "IC1") (pin "17") (pinfunction "SUSPEND_17") (pintype "bidirectional"))
    )
    (net (code "96") (name "unconnected-(IC1-~{CTS}-Pad18)") (class "Default")
      (node (ref "IC1") (pin "18") (pinfunction "~{CTS}_18") (pintype "bidirectional"))
    )
    (net (code "97") (name "unconnected-(IC1-~{DCD}-Pad24)") (class "Default")
      (node (ref "IC1") (pin "24") (pinfunction "~{DCD}_24") (pintype "bidirectional"))
    )
    (net (code "98") (name "unconnected-(IC1-~{DSR}-Pad22)") (class "Default")
      (node (ref "IC1") (pin "22") (pinfunction "~{DSR}_22") (pintype "bidirectional"))
    )
    (net (code "99") (name "unconnected-(IC1-~{RESET}-Pad9)") (class "Default")
      (node (ref "IC1") (pin "9") (pinfunction "~{RESET}_9") (pintype "bidirectional"))
    )
    (net (code "100") (name "unconnected-(IC1-~{RI}-Pad1)") (class "Default")
      (node (ref "IC1") (pin "1") (pinfunction "~{RI}_1") (pintype "bidirectional"))
    )
    (net (code "101") (name "unconnected-(IC1-~{SUSPEND}-Pad15)") (class "Default")
      (node (ref "IC1") (pin "15") (pinfunction "~{SUSPEND}_15") (pintype "bidirectional"))
    )
    (net (code "102") (name "unconnected-(J1-Pad4)") (class "Default")
      (node (ref "J1") (pin "4") (pinfunction "4_4") (pintype "passive"))
    )
    (net (code "103") (name "unconnected-(J2-Pad1)") (class "Default")
      (node (ref "J2") (pin "1") (pinfunction "1_1") (pintype "bidirectional"))
    )
    (net (code "104") (name "unconnected-(J2-Pad6)") (class "Default")
      (node (ref "J2") (pin "6") (pinfunction "6_6") (pintype "bidirectional"))
    )
    (net (code "105") (name "unconnected-(J2-Pad7)") (class "Default")
      (node (ref "J2") (pin "7") (pinfunction "7_7") (pintype "bidirectional"))
    )
    (net (code "106") (name "unconnected-(JP1-Pad18)") (class "Default")
      (node (ref "JP1") (pin "18") (pinfunction "18_18") (pintype "passive"))
    )
    (net (code "107") (name "unconnected-(PAD3-P-Pad1)") (class "Default")
      (node (ref "PAD3") (pin "1") (pinfunction "P_1") (pintype "passive"))
    )
    (net (code "108") (name "unconnected-(S2-1.2-Pad2)") (class "Default")
      (node (ref "S2") (pin "2") (pinfunction "1.2_2") (pintype "passive"))
    )
    (net (code "109") (name "unconnected-(S2-2.2-Pad4)") (class "Default")
      (node (ref "S2") (pin "4") (pinfunction "2.2_4") (pintype "passive"))
    )
    (net (code "110") (name "unconnected-(S2-SH-Pad5)") (class "Default")
      (node (ref "S2") (pin "5") (pinfunction "SH_5") (pintype "passive"))
    )
    (net (code "111") (name "unconnected-(S3-1.2-Pad2)") (class "Default")
      (node (ref "S3") (pin "2") (pinfunction "1.2_2") (pintype "passive"))
    )
    (net (code "112") (name "unconnected-(S3-2.2-Pad4)") (class "Default")
      (node (ref "S3") (pin "4") (pinfunction "2.2_4") (pintype "passive"))
    )
    (net (code "113") (name "unconnected-(S3-SH-Pad5)") (class "Default")
      (node (ref "S3") (pin "5") (pinfunction "SH_5") (pintype "passive"))
    )
    (net (code "114") (name "unconnected-(S4-1.2-Pad2)") (class "Default")
      (node (ref "S4") (pin "2") (pinfunction "1.2_2") (pintype "passive"))
    )
    (net (code "115") (name "unconnected-(S4-2.2-Pad4)") (class "Default")
      (node (ref "S4") (pin "4") (pinfunction "2.2_4") (pintype "passive"))
    )
    (net (code "116") (name "unconnected-(S4-SH-Pad5)") (class "Default")
      (node (ref "S4") (pin "5") (pinfunction "SH_5") (pintype "passive"))
    )
    (net (code "117") (name "unconnected-(S5-1.2-Pad2)") (class "Default")
      (node (ref "S5") (pin "2") (pinfunction "1.2_2") (pintype "passive"))
    )
    (net (code "118") (name "unconnected-(S5-2.2-Pad4)") (class "Default")
      (node (ref "S5") (pin "4") (pinfunction "2.2_4") (pintype "passive"))
    )
    (net (code "119") (name "unconnected-(S5-SH-Pad5)") (class "Default")
      (node (ref "S5") (pin "5") (pinfunction "SH_5") (pintype "passive"))
    )
    (net (code "120") (name "unconnected-(U1-CLK-Pad20)") (class "Default")
      (node (ref "U1") (pin "20") (pinfunction "CLK_20") (pintype "bidirectional"))
    )
    (net (code "121") (name "unconnected-(U1-CMD-Pad19)") (class "Default")
      (node (ref "U1") (pin "19") (pinfunction "CMD_19") (pintype "bidirectional"))
    )
    (net (code "122") (name "unconnected-(U1-NC-Pad32)") (class "Default")
      (node (ref "U1") (pin "32") (pinfunction "NC_32") (pintype "bidirectional"))
    )
    (net (code "123") (name "unconnected-(U1-SD1-Pad22)") (class "Default")
      (node (ref "U1") (pin "22") (pinfunction "SD1_22") (pintype "bidirectional"))
    )
    (net (code "124") (name "unconnected-(U1-SD2-Pad17)") (class "Default")
      (node (ref "U1") (pin "17") (pinfunction "SD2_17") (pintype "bidirectional"))
    )
    (net (code "125") (name "unconnected-(U1-SD3-Pad18)") (class "Default")
      (node (ref "U1") (pin "18") (pinfunction "SD3_18") (pintype "bidirectional"))
    )
    (net (code "126") (name "unconnected-(U1-SDO-Pad21)") (class "Default")
      (node (ref "U1") (pin "21") (pinfunction "SDO_21") (pintype "bidirectional"))
    )
    (net (code "127") (name "unconnected-(U1-SENSOR_VN-Pad5)") (class "Default")
      (node (ref "U1") (pin "5") (pinfunction "SENSOR_VN_5") (pintype "input"))
    )
    (net (code "128") (name "unconnected-(U1-SENSOR_VP-Pad4)") (class "Default")
      (node (ref "U1") (pin "4") (pinfunction "SENSOR_VP_4") (pintype "input"))
    )
    (net (code "129") (name "unconnected-(U2-#RESET-Pad3)") (class "Default")
      (node (ref "U2") (pin "3") (pinfunction "#RESET_3") (pintype "bidirectional"))
    )
    (net (code "130") (name "unconnected-(U2-A0-Pad1)") (class "Default")
      (node (ref "U2") (pin "1") (pinfunction "A0_1") (pintype "bidirectional"))
    )
    (net (code "131") (name "unconnected-(U2-A1-Pad2)") (class "Default")
      (node (ref "U2") (pin "2") (pinfunction "A1_2") (pintype "bidirectional"))
    )
    (net (code "132") (name "unconnected-(U2-A2-Pad21)") (class "Default")
      (node (ref "U2") (pin "21") (pinfunction "A2_21") (pintype "bidirectional"))
    )
    (net (code "133") (name "unconnected-(U7-P4-Pad4)") (class "Default")
      (node (ref "U7") (pin "4") (pinfunction "P4_4") (pintype "bidirectional"))
    )
  )
)
